# Intar_Receiver_Module.net
KiCad netlist of a schematic drawn in EAGLE
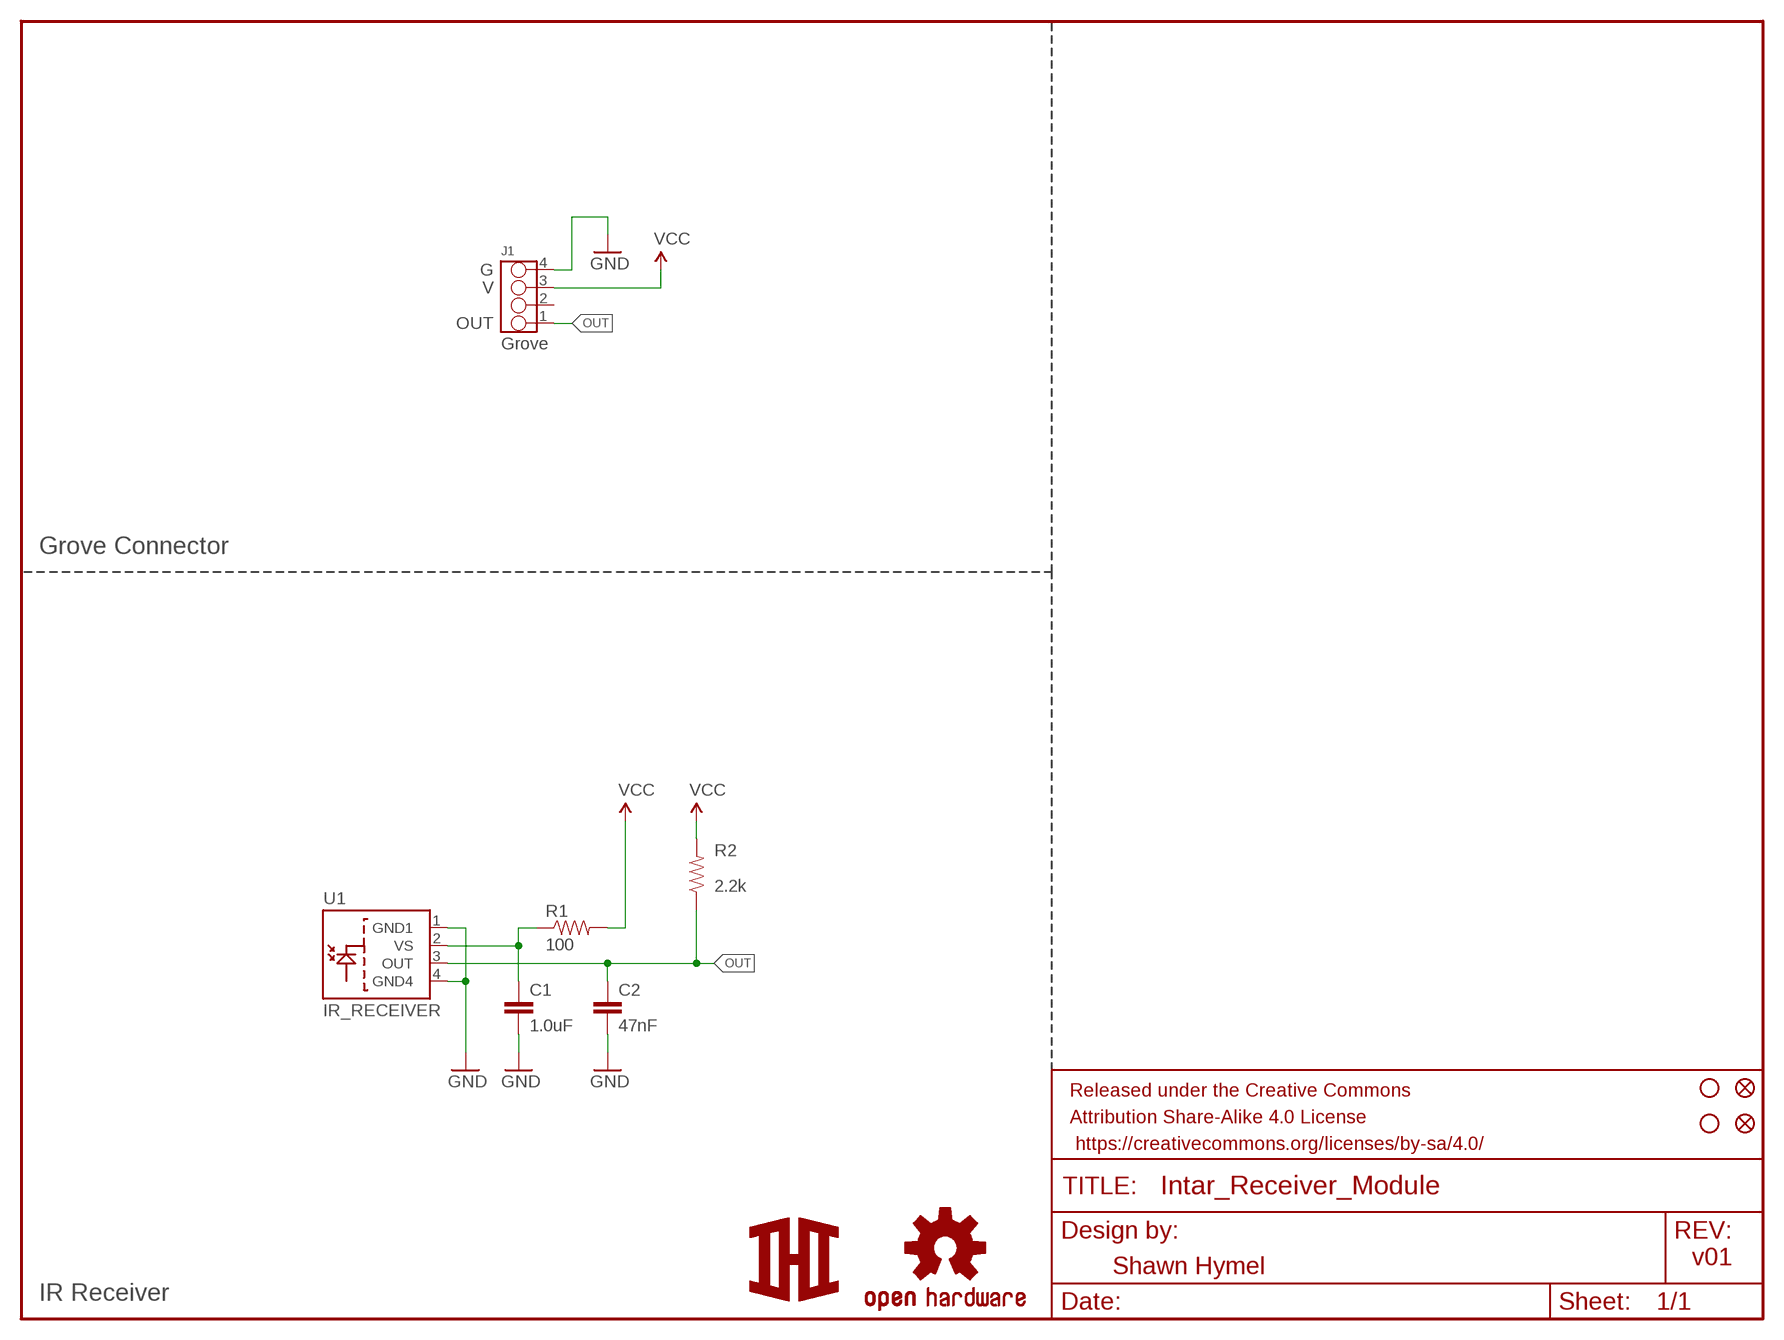
[diagram p0: schematic, sheet 1]

(export (version "E")
  (design (tool "Eeschema 10.0.6"))
  (components
    (comp (ref "C1")
      (value "1.0uF")
      (footprint "eagle-import:0603-CAP")
      (libsource (lib "eagle-import") (part "1.0UF-16V-10%(0603)"))
    )
    (comp (ref "C2")
      (value "47nF")
      (footprint "eagle-import:0603-CAP")
      (libsource (lib "eagle-import") (part "47NF(0.047UF/47000PF)-25V-5%(0603)SMD"))
    )
    (comp (ref "FID1")
      (value "FIDUCIAL1X2")
      (footprint "eagle-import:FIDUCIAL-1X2")
      (libsource (lib "eagle-import") (part "FIDUCIAL1X2"))
    )
    (comp (ref "FID2")
      (value "FIDUCIAL1X2")
      (footprint "eagle-import:FIDUCIAL-1X2")
      (libsource (lib "eagle-import") (part "FIDUCIAL1X2"))
    )
    (comp (ref "FRAME1")
      (value "FRAME-LETTER")
      (footprint "eagle-import:CREATIVE_COMMONS")
      (libsource (lib "eagle-import") (part "FRAME-LETTER"))
    )
    (comp (ref "J1")
      (value "GROVE-4P-2.0-3470130P1")
      (footprint "eagle-import:4P-2.0")
      (libsource (lib "eagle-import") (part "GROVE-4P-2.0-3470130P1"))
    )
    (comp (ref "LOGO1")
      (value "OSHW-LOGOS")
      (footprint "eagle-import:OSHW-LOGO-S")
      (libsource (lib "eagle-import") (part "OSHW-LOGOS"))
    )
    (comp (ref "R1")
      (value "100")
      (footprint "eagle-import:0603-RES")
      (libsource (lib "eagle-import") (part "100OHM-1/10W-1%(0603)"))
    )
    (comp (ref "R2")
      (value "2.2k")
      (footprint "eagle-import:0603-RES")
      (libsource (lib "eagle-import") (part "2.2KOHM-1/10W-1%(0603)"))
    )
    (comp (ref "STANDOFF1")
      (value "STAND-OFF")
      (footprint "eagle-import:STAND-OFF")
      (libsource (lib "eagle-import") (part "STAND-OFF"))
    )
    (comp (ref "STANDOFF2")
      (value "STAND-OFF")
      (footprint "eagle-import:STAND-OFF")
      (libsource (lib "eagle-import") (part "STAND-OFF"))
    )
    (comp (ref "U$1")
      (value "LOGOSM")
      (footprint "eagle-import:LOGO_SM")
      (libsource (lib "eagle-import") (part "LOGOSM"))
    )
    (comp (ref "U1")
      (value "IR_RECEIVER")
      (footprint "eagle-import:TSOP754XXW")
      (libsource (lib "eagle-import") (part "IR_RECEIVER"))
    )
  )
  (nets
    (net (code "1") (name "GND") (class "Default")
      (node (ref "C1") (pin "2") (pinfunction "2_2") (pintype "passive"))
      (node (ref "C2") (pin "2") (pinfunction "2_2") (pintype "passive"))
      (node (ref "J1") (pin "4") (pinfunction "4_4") (pintype "bidirectional"))
      (node (ref "U1") (pin "1") (pinfunction "GND1_1") (pintype "bidirectional"))
      (node (ref "U1") (pin "4") (pinfunction "GND4_4") (pintype "bidirectional"))
    )
    (net (code "2") (name "Net-(U1-VS)") (class "Default")
      (node (ref "C1") (pin "1") (pinfunction "1_1") (pintype "passive"))
      (node (ref "R1") (pin "1") (pinfunction "1_1") (pintype "passive"))
      (node (ref "U1") (pin "2") (pinfunction "VS_2") (pintype "bidirectional"))
    )
    (net (code "3") (name "OUT") (class "Default")
      (node (ref "C2") (pin "1") (pinfunction "1_1") (pintype "passive"))
      (node (ref "J1") (pin "1") (pinfunction "1_1") (pintype "bidirectional"))
      (node (ref "R2") (pin "1") (pinfunction "1_1") (pintype "passive"))
      (node (ref "U1") (pin "3") (pinfunction "OUT_3") (pintype "bidirectional"))
    )
    (net (code "4") (name "VCC") (class "Default")
      (node (ref "J1") (pin "3") (pinfunction "3_3") (pintype "bidirectional"))
      (node (ref "R1") (pin "2") (pinfunction "2_2") (pintype "passive"))
      (node (ref "R2") (pin "2") (pinfunction "2_2") (pintype "passive"))
    )
    (net (code "5") (name "unconnected-(J1-Pad2)") (class "Default")
      (node (ref "J1") (pin "2") (pinfunction "2_2") (pintype "bidirectional"))
    )
  )
)
